# POWER.net
KiCad netlist of a schematic drawn in Altium Designer
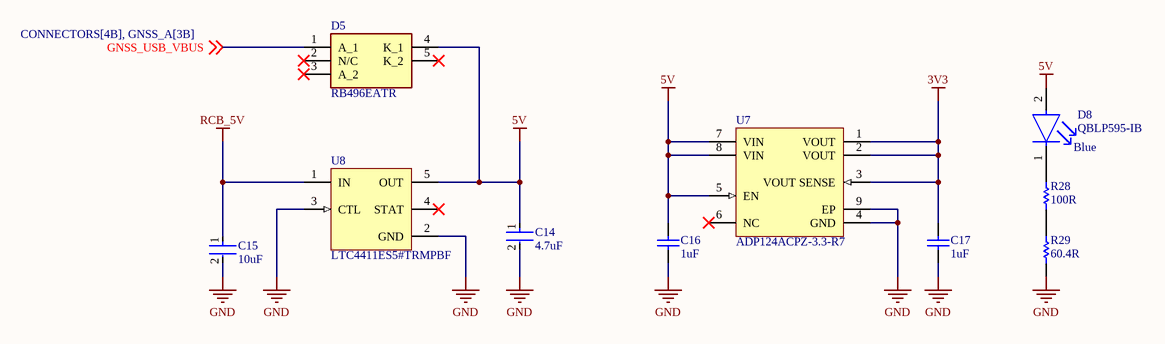
[diagram p0: POWER.SchDoc]

(export (version "E")
  (design (tool "Eeschema 10.0.6"))
  (components
    (comp (ref "C14")
      (value "4.7uF")
      (footprint "FP-C1005-050-0_15-MFG")
      (description "CAP CER 4.7UF 10V X5R 0402")
      (fields (field (name "TOLERANCE") "10%"))
      (libsource (lib "Altium Content Vault") (part "b4654b650e69147ec39a6b967a45e02"))
    )
    (comp (ref "C15")
      (value "10uF")
      (footprint "FP-0603-L_1_6_0_2-W_0_8_0-MFG")
      (description "Multilayer Ceramic Capacitor 10uF 16V X5R 20% SMD 0603 T/R")
      (fields (field (name "TOLERANCE") "20%"))
      (libsource (lib "Altium Content Vault") (part "b4654b650e69147ec39a6b967a45e02"))
    )
    (comp (ref "C16")
      (value "1uF")
      (footprint "CAPC1005X55X25ML05T10")
      (fields (field (name "PART NUMBER") "GRM155C80J105KE15D") (field (name "MANUFACTURER") "Murata"))
      (libsource (lib "Altium Content Vault") (part "CAP"))
    )
    (comp (ref "C17")
      (value "1uF")
      (footprint "CAPC1005X55X25ML05T10")
      (fields (field (name "PART NUMBER") "GRM155C80J105KE15D") (field (name "MANUFACTURER") "Murata"))
      (libsource (lib "Altium Content Vault") (part "CAP"))
    )
    (comp (ref "D5")
      (value "RB496EATR")
      (footprint "SamacSys:SOT95P280X100-5N")
      (description "Schottky Diode")
      (fields (field (name "MOUSER PART NUMBER") "755-RB496EATR"))
      (libsource (lib "*") (part "RB496EATR"))
    )
    (comp (ref "D8")
      (value "QBLP595-IB")
      (footprint "FP-QBLP595-IB-MFG")
      (description "LED BLUE CLEAR 0402 SMD")
      (fields (field (name "COLOR") "Blue"))
      (libsource (lib "Altium Content Vault") (part "8706943c75ba83719d021d2fdc84c58"))
    )
    (comp (ref "R28")
      (value "100R")
      (footprint "RESC1005X40X25LL05T05")
      (description "Chip Resistor, 100 Ohm, +/- 1%, 100 mW, -55 to 155 degC, 0402 (1005 Metric), RoHS, Tape and Reel")
      (fields (field (name "MANUFACTURER") "Basic Passives") (field (name "TOLERANCE") "1%"))
      (libsource (lib "Altium Content Vault") (part "RES-2"))
    )
    (comp (ref "R29")
      (value "60.4R")
      (footprint "RESC1005X40X25ML05T05")
      (fields (field (name "PART NUMBER") "ERJ-2RKF6040X") (field (name "MANUFACTURER") "Panasonic"))
      (libsource (lib "Altium Content Vault") (part "RES"))
    )
    (comp (ref "U7")
      (value "ADP124ACPZ-3.3-R7")
      (footprint "ADI-CP-8-8_V")
      (fields (field (name "MANUFACTURER") "Analog Devices"))
      (libsource (lib "Altium Content Vault") (part "ADI-ADP124-CP-8-8"))
    )
    (comp (ref "U8")
      (value "LTC4411ES5#TRMPBF")
      (footprint "LT-S5-5-TSOT-23_N")
      (fields (field (name "MANUFACTURER") "Linear Technology"))
      (libsource (lib "Altium Content Vault") (part "LT-LTC4411-S5-5"))
    )
  )
  (nets
    (net (code "1") (name "3V3") (class "Default")
      (node (ref "C17") (pin "2") (pinfunction "2_2") (pintype "passive"))
      (node (ref "U7") (pin "1") (pinfunction "VOUT_1") (pintype "power_in"))
      (node (ref "U7") (pin "2") (pinfunction "VOUT_2") (pintype "power_in"))
      (node (ref "U7") (pin "3") (pinfunction "VOUT_SENSE_3") (pintype "input"))
    )
    (net (code "2") (name "5V") (class "Default")
      (node (ref "C14") (pin "1") (pinfunction "1_1") (pintype "passive"))
      (node (ref "C16") (pin "2") (pinfunction "2_2") (pintype "passive"))
      (node (ref "D5") (pin "4") (pinfunction "K_1_4") (pintype "passive"))
      (node (ref "D8") (pin "2") (pinfunction "A_2") (pintype "passive"))
      (node (ref "U7") (pin "5") (pinfunction "EN_5") (pintype "input"))
      (node (ref "U7") (pin "7") (pinfunction "VIN_7") (pintype "power_in"))
      (node (ref "U7") (pin "8") (pinfunction "VIN_8") (pintype "power_in"))
      (node (ref "U8") (pin "5") (pinfunction "OUT_5") (pintype "power_in"))
    )
    (net (code "3") (name "GND") (class "Default")
      (node (ref "C14") (pin "2") (pinfunction "2_2") (pintype "passive"))
      (node (ref "C15") (pin "2") (pinfunction "2_2") (pintype "passive"))
      (node (ref "C16") (pin "1") (pinfunction "1_1") (pintype "passive"))
      (node (ref "C17") (pin "1") (pinfunction "1_1") (pintype "passive"))
      (node (ref "R29") (pin "2") (pinfunction "2_2") (pintype "passive"))
      (node (ref "U7") (pin "4") (pinfunction "GND_4") (pintype "power_in"))
      (node (ref "U7") (pin "9") (pinfunction "EP_9") (pintype "power_in"))
      (node (ref "U8") (pin "2") (pinfunction "GND_2") (pintype "power_in"))
      (node (ref "U8") (pin "3") (pinfunction "CTL_3") (pintype "input"))
    )
    (net (code "4") (name "GNSS_USB_VBUS") (class "Default")
      (node (ref "D5") (pin "1") (pinfunction "A_1_1") (pintype "passive"))
    )
    (net (code "5") (name "Net-(D8-C)") (class "Default")
      (node (ref "D8") (pin "1") (pinfunction "C_1") (pintype "passive"))
      (node (ref "R28") (pin "2") (pinfunction "2_2") (pintype "passive"))
    )
    (net (code "6") (name "Net-(R28-Pad1)") (class "Default")
      (node (ref "R28") (pin "1") (pinfunction "1_1") (pintype "passive"))
      (node (ref "R29") (pin "1") (pinfunction "1_1") (pintype "passive"))
    )
    (net (code "7") (name "RCB_5V") (class "Default")
      (node (ref "C15") (pin "1") (pinfunction "1_1") (pintype "passive"))
      (node (ref "U8") (pin "1") (pinfunction "IN_1") (pintype "power_in"))
    )
    (net (code "8") (name "unconnected-(D5-A_2-Pad3)") (class "Default")
      (node (ref "D5") (pin "3") (pinfunction "A_2_3") (pintype "passive+no_connect"))
    )
    (net (code "9") (name "unconnected-(D5-K_2-Pad5)") (class "Default")
      (node (ref "D5") (pin "5") (pinfunction "K_2_5") (pintype "passive+no_connect"))
    )
    (net (code "10") (name "unconnected-(D5-N{slash}C-Pad2)") (class "Default")
      (node (ref "D5") (pin "2") (pinfunction "N/C_2") (pintype "passive+no_connect"))
    )
    (net (code "11") (name "unconnected-(U7-NC-Pad6)") (class "Default")
      (node (ref "U7") (pin "6") (pinfunction "NC_6") (pintype "passive+no_connect"))
    )
    (net (code "12") (name "unconnected-(U8-STAT-Pad4)") (class "Default")
      (node (ref "U8") (pin "4") (pinfunction "STAT_4") (pintype "tri_state+no_connect"))
    )
  )
)
